# nimbusrtc.net
KiCad netlist of a schematic drawn in EAGLE
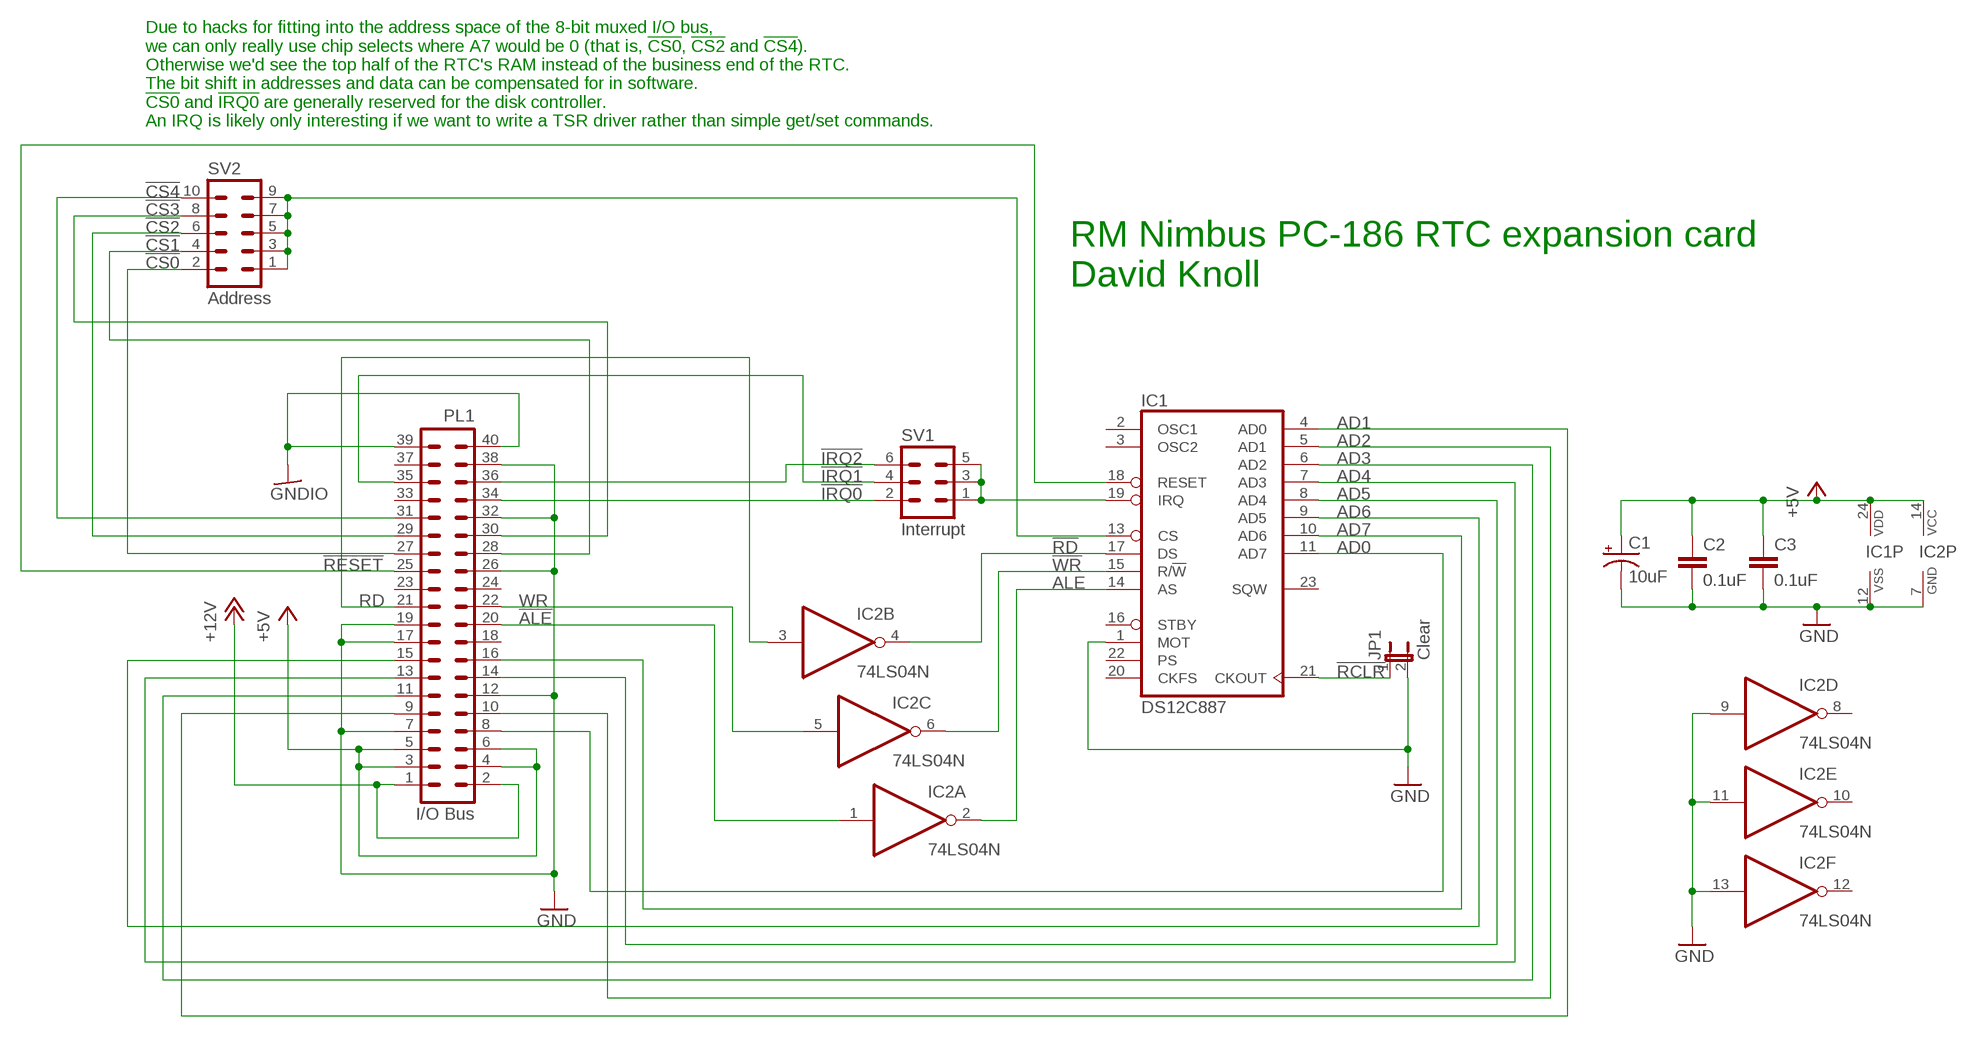
[diagram p0: schematic, sheet 1]

(export (version "E")
  (design (tool "Eeschema 10.0.6"))
  (components
    (comp (ref "C1")
      (value "10uF")
      (footprint "eagle-import:E2,5-6")
      (libsource (lib "eagle-import") (part "CPOL-USE2.5-6"))
    )
    (comp (ref "C2")
      (value "0.1uF")
      (footprint "eagle-import:C050-024X044")
      (libsource (lib "eagle-import") (part "C-EU050-024X044"))
    )
    (comp (ref "C3")
      (value "0.1uF")
      (footprint "eagle-import:C050-024X044")
      (libsource (lib "eagle-import") (part "C-EU050-024X044"))
    )
    (comp (ref "IC1")
      (value "DS12C887")
      (footprint "eagle-import:DIL24")
      (libsource (lib "eagle-import") (part "146818A"))
    )
    (comp (ref "IC2")
      (value "74LS04N")
      (footprint "eagle-import:DIL14")
      (libsource (lib "eagle-import") (part "7404NLS"))
    )
    (comp (ref "JP1")
      (value "Clear")
      (footprint "eagle-import:JP1")
      (libsource (lib "eagle-import") (part "JP1E"))
    )
    (comp (ref "PL1")
      (value "I/O Bus")
      (footprint "eagle-import:40H")
      (libsource (lib "eagle-import") (part "40H"))
    )
    (comp (ref "SV1")
      (value "Interrupt")
      (footprint "eagle-import:MA03-2")
      (libsource (lib "eagle-import") (part "MA03-2"))
    )
    (comp (ref "SV2")
      (value "Address")
      (footprint "eagle-import:MA05-2")
      (libsource (lib "eagle-import") (part "MA05-2"))
    )
  )
  (nets
    (net (code "1") (name "+5V") (class "Default")
      (node (ref "C1") (pin "+") (pinfunction "+_+") (pintype "passive"))
      (node (ref "C2") (pin "1") (pinfunction "1_1") (pintype "passive"))
      (node (ref "C3") (pin "1") (pinfunction "1_1") (pintype "passive"))
      (node (ref "IC1") (pin "24") (pinfunction "VDD_24") (pintype "power_in"))
      (node (ref "IC2") (pin "14") (pinfunction "VCC_14") (pintype "power_in"))
      (node (ref "PL1") (pin "3") (pinfunction "3_3") (pintype "passive"))
      (node (ref "PL1") (pin "4") (pinfunction "4_4") (pintype "passive"))
      (node (ref "PL1") (pin "5") (pinfunction "5_5") (pintype "passive"))
      (node (ref "PL1") (pin "6") (pinfunction "6_6") (pintype "passive"))
    )
    (net (code "2") (name "+12V") (class "Default")
      (node (ref "PL1") (pin "1") (pinfunction "1_1") (pintype "passive"))
      (node (ref "PL1") (pin "2") (pinfunction "2_2") (pintype "passive"))
    )
    (net (code "3") (name "/AD0") (class "Default")
      (node (ref "IC1") (pin "11") (pinfunction "AD7_11") (pintype "bidirectional"))
      (node (ref "PL1") (pin "8") (pinfunction "8_8") (pintype "passive"))
    )
    (net (code "4") (name "/AD1") (class "Default")
      (node (ref "IC1") (pin "4") (pinfunction "AD0_4") (pintype "bidirectional"))
      (node (ref "PL1") (pin "9") (pinfunction "9_9") (pintype "passive"))
    )
    (net (code "5") (name "/AD2") (class "Default")
      (node (ref "IC1") (pin "5") (pinfunction "AD1_5") (pintype "bidirectional"))
      (node (ref "PL1") (pin "10") (pinfunction "10_10") (pintype "passive"))
    )
    (net (code "6") (name "/AD3") (class "Default")
      (node (ref "IC1") (pin "6") (pinfunction "AD2_6") (pintype "bidirectional"))
      (node (ref "PL1") (pin "11") (pinfunction "11_11") (pintype "passive"))
    )
    (net (code "7") (name "/AD4") (class "Default")
      (node (ref "IC1") (pin "7") (pinfunction "AD3_7") (pintype "bidirectional"))
      (node (ref "PL1") (pin "13") (pinfunction "13_13") (pintype "passive"))
    )
    (net (code "8") (name "/AD5") (class "Default")
      (node (ref "IC1") (pin "8") (pinfunction "AD4_8") (pintype "bidirectional"))
      (node (ref "PL1") (pin "14") (pinfunction "14_14") (pintype "passive"))
    )
    (net (code "9") (name "/AD6") (class "Default")
      (node (ref "IC1") (pin "9") (pinfunction "AD5_9") (pintype "bidirectional"))
      (node (ref "PL1") (pin "15") (pinfunction "15_15") (pintype "passive"))
    )
    (net (code "10") (name "/AD7") (class "Default")
      (node (ref "IC1") (pin "10") (pinfunction "AD6_10") (pintype "bidirectional"))
      (node (ref "PL1") (pin "16") (pinfunction "16_16") (pintype "passive"))
    )
    (net (code "11") (name "/ALE") (class "Default")
      (node (ref "IC1") (pin "14") (pinfunction "AS_14") (pintype "input"))
      (node (ref "IC2") (pin "2") (pinfunction "O_2") (pintype "output"))
    )
    (net (code "12") (name "/RD") (class "Default")
      (node (ref "IC2") (pin "3") (pinfunction "I_3") (pintype "input"))
      (node (ref "PL1") (pin "21") (pinfunction "21_21") (pintype "passive"))
    )
    (net (code "13") (name "/WR") (class "Default")
      (node (ref "IC2") (pin "5") (pinfunction "I_5") (pintype "input"))
      (node (ref "PL1") (pin "22") (pinfunction "22_22") (pintype "passive"))
    )
    (net (code "14") (name "/~{ALE}") (class "Default")
      (node (ref "IC2") (pin "1") (pinfunction "I_1") (pintype "input"))
      (node (ref "PL1") (pin "20") (pinfunction "20_20") (pintype "passive"))
    )
    (net (code "15") (name "/~{CS0}") (class "Default")
      (node (ref "PL1") (pin "27") (pinfunction "27_27") (pintype "passive"))
      (node (ref "SV2") (pin "2") (pinfunction "2_2") (pintype "passive"))
    )
    (net (code "16") (name "/~{CS1}") (class "Default")
      (node (ref "PL1") (pin "28") (pinfunction "28_28") (pintype "passive"))
      (node (ref "SV2") (pin "4") (pinfunction "4_4") (pintype "passive"))
    )
    (net (code "17") (name "/~{CS2}") (class "Default")
      (node (ref "PL1") (pin "29") (pinfunction "29_29") (pintype "passive"))
      (node (ref "SV2") (pin "6") (pinfunction "6_6") (pintype "passive"))
    )
    (net (code "18") (name "/~{CS3}") (class "Default")
      (node (ref "PL1") (pin "30") (pinfunction "30_30") (pintype "passive"))
      (node (ref "SV2") (pin "8") (pinfunction "8_8") (pintype "passive"))
    )
    (net (code "19") (name "/~{CS4}") (class "Default")
      (node (ref "PL1") (pin "31") (pinfunction "31_31") (pintype "passive"))
      (node (ref "SV2") (pin "10") (pinfunction "10_10") (pintype "passive"))
    )
    (net (code "20") (name "/~{IRQ0}") (class "Default")
      (node (ref "PL1") (pin "34") (pinfunction "34_34") (pintype "passive"))
      (node (ref "SV1") (pin "2") (pinfunction "2_2") (pintype "passive"))
    )
    (net (code "21") (name "/~{IRQ1}") (class "Default")
      (node (ref "PL1") (pin "35") (pinfunction "35_35") (pintype "passive"))
      (node (ref "SV1") (pin "4") (pinfunction "4_4") (pintype "passive"))
    )
    (net (code "22") (name "/~{IRQ2}") (class "Default")
      (node (ref "PL1") (pin "36") (pinfunction "36_36") (pintype "passive"))
      (node (ref "SV1") (pin "6") (pinfunction "6_6") (pintype "passive"))
    )
    (net (code "23") (name "/~{RCLR}") (class "Default")
      (node (ref "IC1") (pin "21") (pinfunction "CKOUT_21") (pintype "output"))
      (node (ref "JP1") (pin "1") (pinfunction "1_1") (pintype "passive"))
    )
    (net (code "24") (name "/~{RD}") (class "Default")
      (node (ref "IC1") (pin "17") (pinfunction "DS_17") (pintype "input"))
      (node (ref "IC2") (pin "4") (pinfunction "O_4") (pintype "output"))
    )
    (net (code "25") (name "/~{RESET}") (class "Default")
      (node (ref "IC1") (pin "18") (pinfunction "RESET_18") (pintype "input"))
      (node (ref "PL1") (pin "25") (pinfunction "25_25") (pintype "passive"))
    )
    (net (code "26") (name "/~{WR}") (class "Default")
      (node (ref "IC1") (pin "15") (pinfunction "R/~{W}_15") (pintype "input"))
      (node (ref "IC2") (pin "6") (pinfunction "O_6") (pintype "output"))
    )
    (net (code "27") (name "GND") (class "Default")
      (node (ref "C1") (pin "-") (pinfunction "-_-") (pintype "passive"))
      (node (ref "C2") (pin "2") (pinfunction "2_2") (pintype "passive"))
      (node (ref "C3") (pin "2") (pinfunction "2_2") (pintype "passive"))
      (node (ref "IC1") (pin "1") (pinfunction "MOT_1") (pintype "input"))
      (node (ref "IC1") (pin "12") (pinfunction "VSS_12") (pintype "power_in"))
      (node (ref "IC2") (pin "11") (pinfunction "I_11") (pintype "input"))
      (node (ref "IC2") (pin "13") (pinfunction "I_13") (pintype "input"))
      (node (ref "IC2") (pin "7") (pinfunction "GND_7") (pintype "power_in"))
      (node (ref "IC2") (pin "9") (pinfunction "I_9") (pintype "input"))
      (node (ref "JP1") (pin "2") (pinfunction "2_2") (pintype "passive"))
      (node (ref "PL1") (pin "12") (pinfunction "12_12") (pintype "passive"))
      (node (ref "PL1") (pin "17") (pinfunction "17_17") (pintype "passive"))
      (node (ref "PL1") (pin "19") (pinfunction "19_19") (pintype "passive"))
      (node (ref "PL1") (pin "26") (pinfunction "26_26") (pintype "passive"))
      (node (ref "PL1") (pin "32") (pinfunction "32_32") (pintype "passive"))
      (node (ref "PL1") (pin "38") (pinfunction "38_38") (pintype "passive"))
      (node (ref "PL1") (pin "7") (pinfunction "7_7") (pintype "passive"))
    )
    (net (code "28") (name "GNDIO") (class "Default")
      (node (ref "PL1") (pin "39") (pinfunction "39_39") (pintype "passive"))
      (node (ref "PL1") (pin "40") (pinfunction "40_40") (pintype "passive"))
    )
    (net (code "29") (name "Net-(IC1A-CS)") (class "Default")
      (node (ref "IC1") (pin "13") (pinfunction "CS_13") (pintype "input"))
      (node (ref "SV2") (pin "1") (pinfunction "1_1") (pintype "passive"))
      (node (ref "SV2") (pin "3") (pinfunction "3_3") (pintype "passive"))
      (node (ref "SV2") (pin "5") (pinfunction "5_5") (pintype "passive"))
      (node (ref "SV2") (pin "7") (pinfunction "7_7") (pintype "passive"))
      (node (ref "SV2") (pin "9") (pinfunction "9_9") (pintype "passive"))
    )
    (net (code "30") (name "Net-(IC1A-IRQ)") (class "Default")
      (node (ref "IC1") (pin "19") (pinfunction "IRQ_19") (pintype "output"))
      (node (ref "SV1") (pin "1") (pinfunction "1_1") (pintype "passive"))
      (node (ref "SV1") (pin "3") (pinfunction "3_3") (pintype "passive"))
      (node (ref "SV1") (pin "5") (pinfunction "5_5") (pintype "passive"))
    )
    (net (code "31") (name "unconnected-(IC1A-CKFS-Pad20)") (class "Default")
      (node (ref "IC1") (pin "20") (pinfunction "CKFS_20") (pintype "input"))
    )
    (net (code "32") (name "unconnected-(IC1A-OSC1-Pad2)") (class "Default")
      (node (ref "IC1") (pin "2") (pinfunction "OSC1_2") (pintype "input"))
    )
    (net (code "33") (name "unconnected-(IC1A-OSC2-Pad3)") (class "Default")
      (node (ref "IC1") (pin "3") (pinfunction "OSC2_3") (pintype "passive"))
    )
    (net (code "34") (name "unconnected-(IC1A-PS-Pad22)") (class "Default")
      (node (ref "IC1") (pin "22") (pinfunction "PS_22") (pintype "input"))
    )
    (net (code "35") (name "unconnected-(IC1A-SQW-Pad23)") (class "Default")
      (node (ref "IC1") (pin "23") (pinfunction "SQW_23") (pintype "output"))
    )
    (net (code "36") (name "unconnected-(IC1A-STBY-Pad16)") (class "Default")
      (node (ref "IC1") (pin "16") (pinfunction "STBY_16") (pintype "input"))
    )
    (net (code "37") (name "unconnected-(IC2D-O-Pad8)") (class "Default")
      (node (ref "IC2") (pin "8") (pinfunction "O_8") (pintype "output"))
    )
    (net (code "38") (name "unconnected-(IC2E-O-Pad10)") (class "Default")
      (node (ref "IC2") (pin "10") (pinfunction "O_10") (pintype "output"))
    )
    (net (code "39") (name "unconnected-(IC2F-O-Pad12)") (class "Default")
      (node (ref "IC2") (pin "12") (pinfunction "O_12") (pintype "output"))
    )
    (net (code "40") (name "unconnected-(PL1-Pad18)") (class "Default")
      (node (ref "PL1") (pin "18") (pinfunction "18_18") (pintype "passive"))
    )
    (net (code "41") (name "unconnected-(PL1-Pad23)") (class "Default")
      (node (ref "PL1") (pin "23") (pinfunction "23_23") (pintype "passive"))
    )
    (net (code "42") (name "unconnected-(PL1-Pad24)") (class "Default")
      (node (ref "PL1") (pin "24") (pinfunction "24_24") (pintype "passive"))
    )
    (net (code "43") (name "unconnected-(PL1-Pad33)") (class "Default")
      (node (ref "PL1") (pin "33") (pinfunction "33_33") (pintype "passive"))
    )
    (net (code "44") (name "unconnected-(PL1-Pad37)") (class "Default")
      (node (ref "PL1") (pin "37") (pinfunction "37_37") (pintype "passive"))
    )
  )
)
